# passion-v2-1.net
KiCad netlist of a schematic drawn in EAGLE
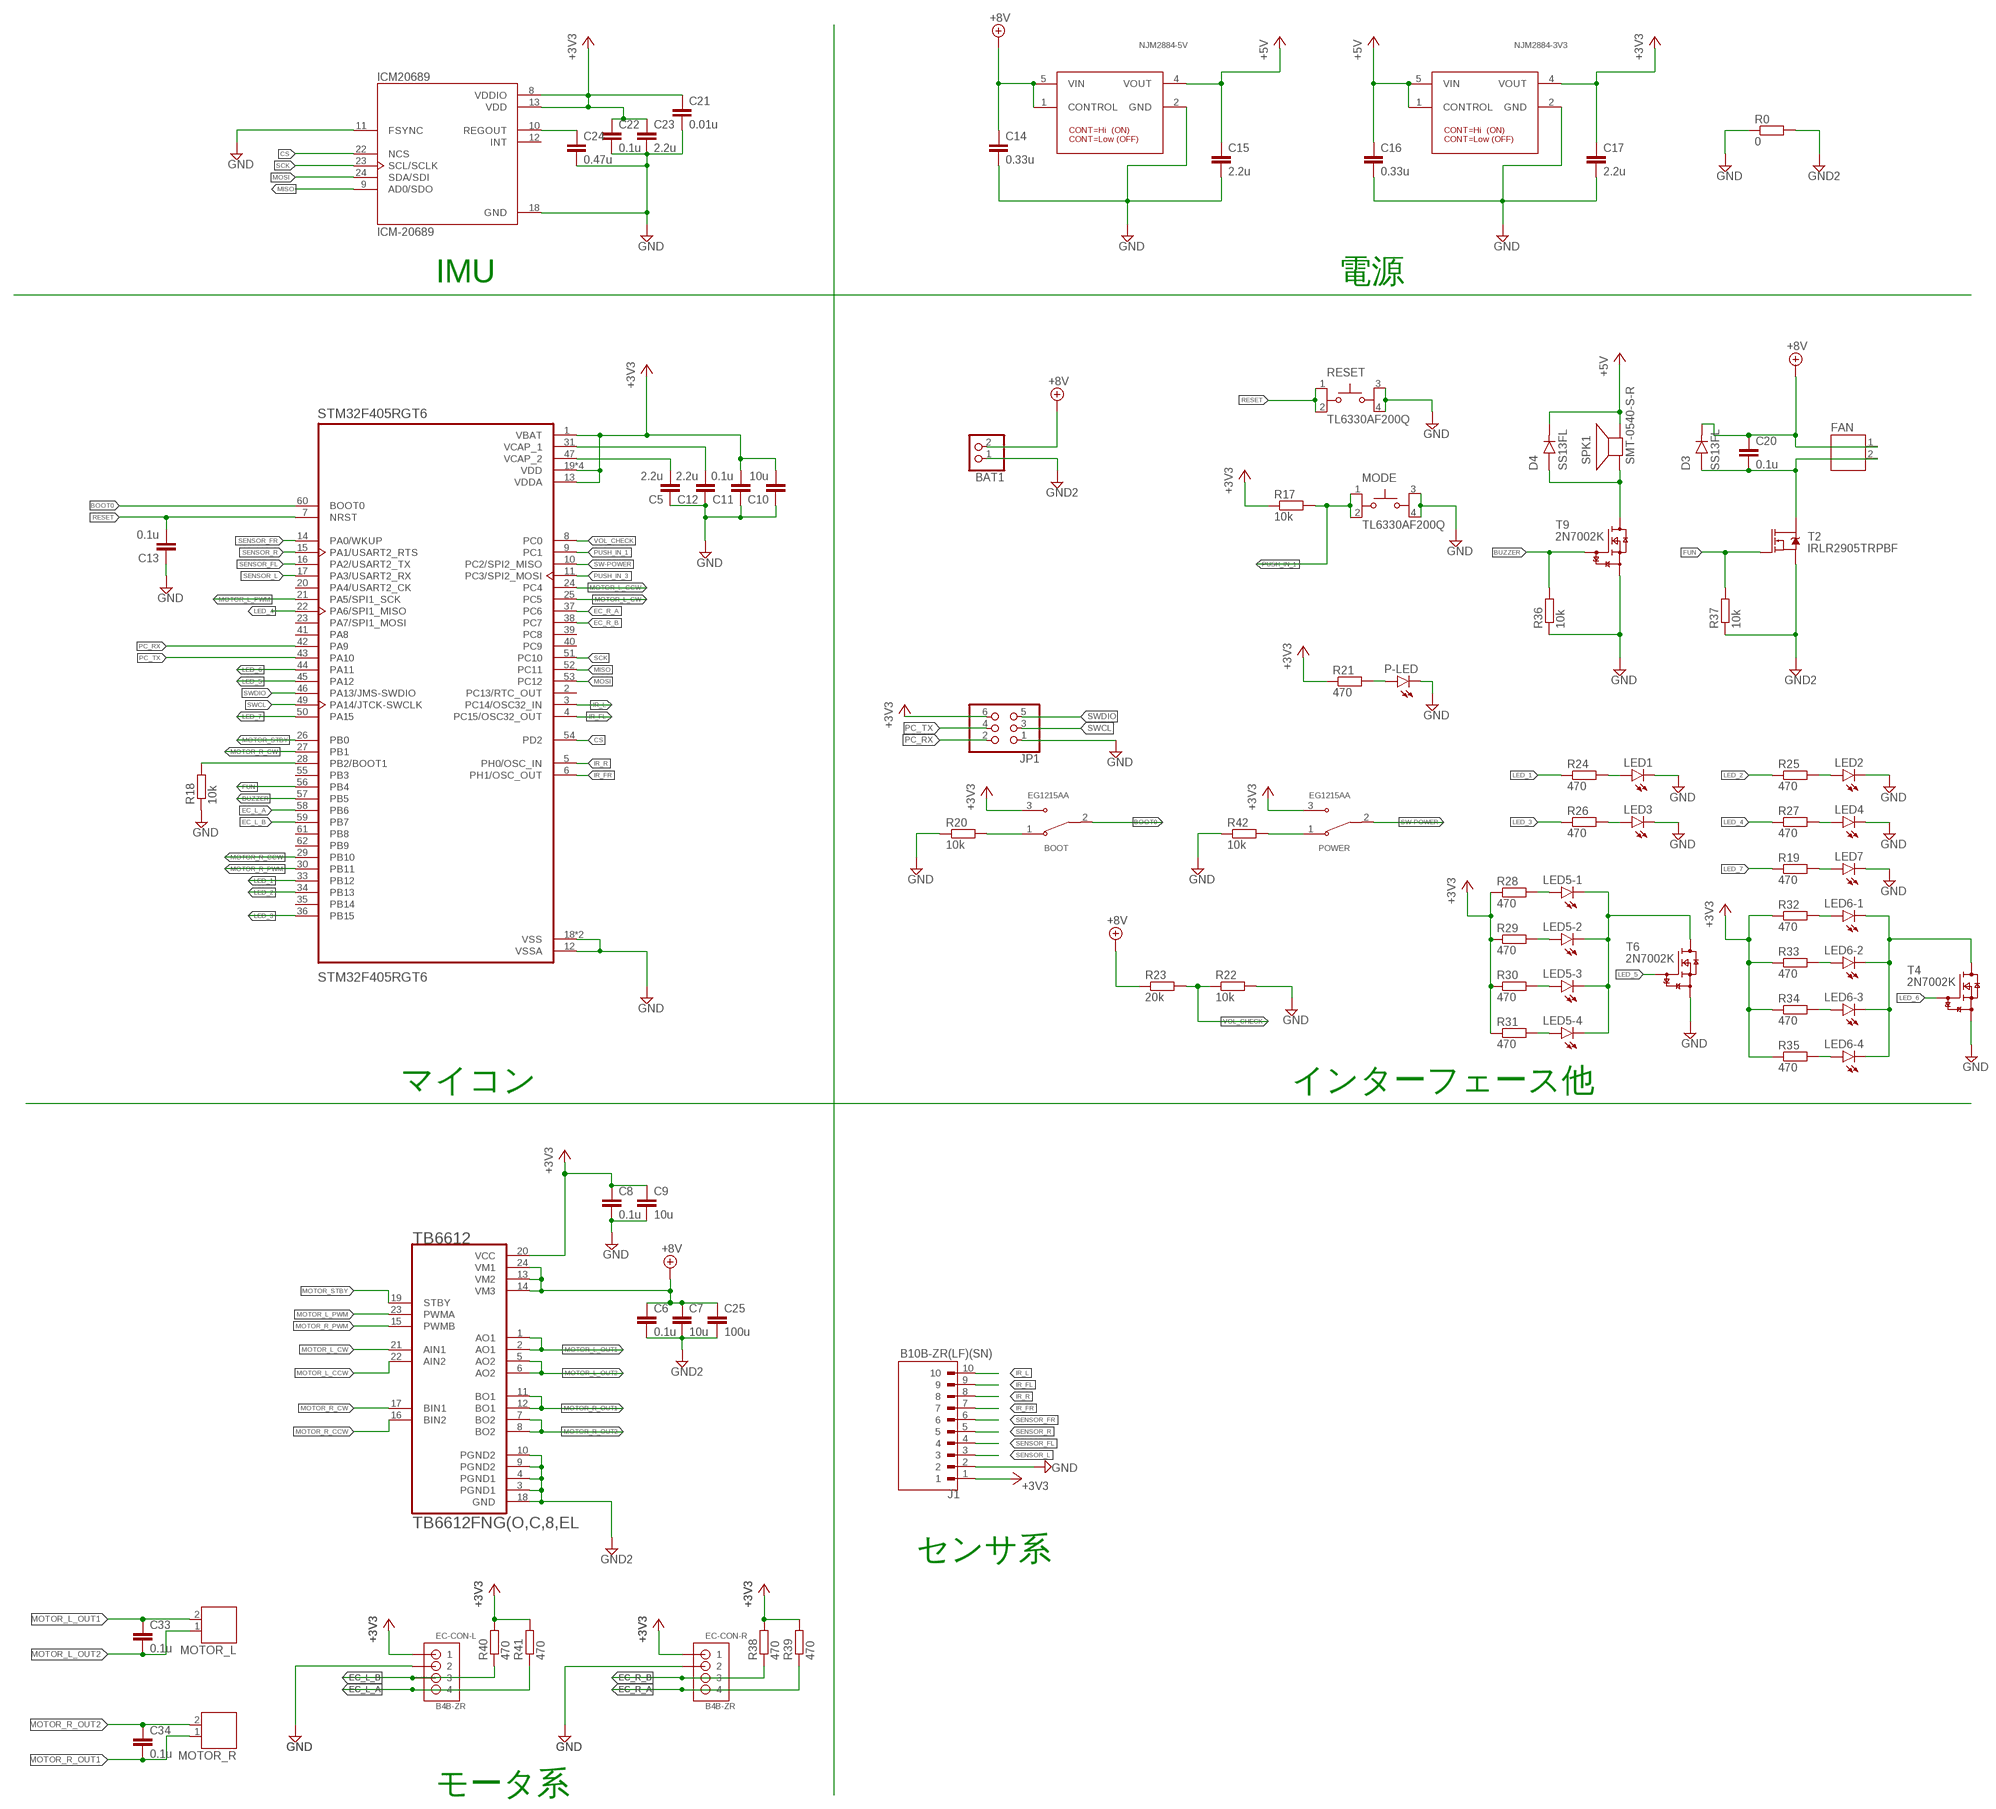
[diagram p0: schematic, sheet 1]

(export (version "E")
  (design (tool "Eeschema 10.0.6"))
  (components
    (comp (ref "BAT1")
      (value "PINHD-1X2")
      (footprint "eagle-import:1X02")
      (libsource (lib "eagle-import") (part "PINHD-1X2"))
    )
    (comp (ref "BOOT")
      (value "EG1215AA")
      (footprint "eagle-import:SW_EG1215AA")
      (fields (field (name "MF") "E-Switch"))
      (libsource (lib "eagle-import") (part "EG1215AA"))
    )
    (comp (ref "C5")
      (value "2.2u")
      (footprint "eagle-import:C0603")
      (libsource (lib "eagle-import") (part "C-EUC0603"))
    )
    (comp (ref "C6")
      (value "0.1u")
      (footprint "eagle-import:C0603")
      (libsource (lib "eagle-import") (part "C-EUC0603"))
    )
    (comp (ref "C7")
      (value "10u")
      (footprint "eagle-import:C0603")
      (libsource (lib "eagle-import") (part "C-EUC0603"))
    )
    (comp (ref "C8")
      (value "0.1u")
      (footprint "eagle-import:C0603")
      (libsource (lib "eagle-import") (part "C-EUC0603"))
    )
    (comp (ref "C9")
      (value "10u")
      (footprint "eagle-import:C0603K")
      (libsource (lib "eagle-import") (part "C-EUC0603K"))
    )
    (comp (ref "C10")
      (value "10u")
      (footprint "eagle-import:C0603")
      (libsource (lib "eagle-import") (part "C-EUC0603"))
    )
    (comp (ref "C11")
      (value "0.1u")
      (footprint "eagle-import:C0603")
      (libsource (lib "eagle-import") (part "C-EUC0603"))
    )
    (comp (ref "C12")
      (value "2.2u")
      (footprint "eagle-import:C0603")
      (libsource (lib "eagle-import") (part "C-EUC0603"))
    )
    (comp (ref "C13")
      (value "0.1u")
      (footprint "eagle-import:C0603")
      (libsource (lib "eagle-import") (part "C-EUC0603"))
    )
    (comp (ref "C14")
      (value "0.33u")
      (footprint "eagle-import:C0603")
      (libsource (lib "eagle-import") (part "C-EUC0603"))
    )
    (comp (ref "C15")
      (value "2.2u")
      (footprint "eagle-import:C0603")
      (libsource (lib "eagle-import") (part "C-EUC0603"))
    )
    (comp (ref "C16")
      (value "0.33u")
      (footprint "eagle-import:C0603")
      (libsource (lib "eagle-import") (part "C-EUC0603"))
    )
    (comp (ref "C17")
      (value "2.2u")
      (footprint "eagle-import:C0603")
      (libsource (lib "eagle-import") (part "C-EUC0603"))
    )
    (comp (ref "C20")
      (value "0.1u")
      (footprint "eagle-import:C0603")
      (libsource (lib "eagle-import") (part "C-EUC0603"))
    )
    (comp (ref "C21")
      (value "0.01u")
      (footprint "eagle-import:C0603")
      (libsource (lib "eagle-import") (part "C-EUC0603"))
    )
    (comp (ref "C22")
      (value "0.1u")
      (footprint "eagle-import:C0603")
      (libsource (lib "eagle-import") (part "C-EUC0603"))
    )
    (comp (ref "C23")
      (value "2.2u")
      (footprint "eagle-import:C0603")
      (libsource (lib "eagle-import") (part "C-EUC0603"))
    )
    (comp (ref "C24")
      (value "0.47u")
      (footprint "eagle-import:C0603")
      (libsource (lib "eagle-import") (part "C-EUC0603"))
    )
    (comp (ref "C25")
      (value "100u")
      (footprint "eagle-import:C3216")
      (libsource (lib "eagle-import") (part "C-EUC3216"))
    )
    (comp (ref "C33")
      (value "0.1u")
      (footprint "eagle-import:C0603")
      (libsource (lib "eagle-import") (part "C-EUC0603"))
    )
    (comp (ref "C34")
      (value "0.1u")
      (footprint "eagle-import:C0603")
      (libsource (lib "eagle-import") (part "C-EUC0603"))
    )
    (comp (ref "D3")
      (value "SS13FL")
      (footprint "eagle-import:SODFL3617X108N")
      (fields (field (name "MF") "ON Semiconductor"))
      (libsource (lib "eagle-import") (part "SS13FL"))
    )
    (comp (ref "D4")
      (value "SS13FL")
      (footprint "eagle-import:SODFL3617X108N")
      (fields (field (name "MF") "ON Semiconductor"))
      (libsource (lib "eagle-import") (part "SS13FL"))
    )
    (comp (ref "EC-CON-L")
      (value "B4B-ZR")
      (footprint "eagle-import:B4B-ZR")
      (libsource (lib "eagle-import") (part "B4B-ZR"))
    )
    (comp (ref "EC-CON-R")
      (value "B4B-ZR")
      (footprint "eagle-import:B4B-ZR")
      (libsource (lib "eagle-import") (part "B4B-ZR"))
    )
    (comp (ref "FAN")
      (value "JST-PH2")
      (footprint "eagle-import:JST-PH2")
      (libsource (lib "eagle-import") (part "JST-PH2"))
    )
    (comp (ref "ICM20689")
      (value "ICM-20689")
      (footprint "eagle-import:QFN50P400X400X95-24N")
      (fields (field (name "MF") "TDK InvenSense"))
      (libsource (lib "eagle-import") (part "ICM-20689"))
    )
    (comp (ref "J1")
      (value "B10B-ZR(LF)(SN)")
      (footprint "eagle-import:JST_B10B-ZR(LF)(SN)")
      (fields (field (name "MF") "JST Sales America Inc."))
      (libsource (lib "eagle-import") (part "B10B-ZR(LF)(SN)"))
    )
    (comp (ref "JP1")
      (value "PINHD-2X3")
      (footprint "eagle-import:2X03")
      (libsource (lib "eagle-import") (part "PINHD-2X3"))
    )
    (comp (ref "LED1")
      (value "LEDCHIPLED_0603")
      (footprint "eagle-import:CHIPLED_0603")
      (libsource (lib "eagle-import") (part "LEDCHIPLED_0603"))
    )
    (comp (ref "LED2")
      (value "LEDCHIPLED_0603")
      (footprint "eagle-import:CHIPLED_0603")
      (libsource (lib "eagle-import") (part "LEDCHIPLED_0603"))
    )
    (comp (ref "LED3")
      (value "LEDCHIPLED_0603")
      (footprint "eagle-import:CHIPLED_0603")
      (libsource (lib "eagle-import") (part "LEDCHIPLED_0603"))
    )
    (comp (ref "LED4")
      (value "LEDCHIPLED_0603")
      (footprint "eagle-import:CHIPLED_0603")
      (libsource (lib "eagle-import") (part "LEDCHIPLED_0603"))
    )
    (comp (ref "LED5-1")
      (value "LEDCHIPLED_0603")
      (footprint "eagle-import:CHIPLED_0603")
      (libsource (lib "eagle-import") (part "LEDCHIPLED_0603"))
    )
    (comp (ref "LED5-2")
      (value "LEDCHIPLED_0603")
      (footprint "eagle-import:CHIPLED_0603")
      (libsource (lib "eagle-import") (part "LEDCHIPLED_0603"))
    )
    (comp (ref "LED5-3")
      (value "LEDCHIPLED_0603")
      (footprint "eagle-import:CHIPLED_0603")
      (libsource (lib "eagle-import") (part "LEDCHIPLED_0603"))
    )
    (comp (ref "LED5-4")
      (value "LEDCHIPLED_0603")
      (footprint "eagle-import:CHIPLED_0603")
      (libsource (lib "eagle-import") (part "LEDCHIPLED_0603"))
    )
    (comp (ref "LED6-1")
      (value "LEDCHIPLED_0603")
      (footprint "eagle-import:CHIPLED_0603")
      (libsource (lib "eagle-import") (part "LEDCHIPLED_0603"))
    )
    (comp (ref "LED6-2")
      (value "LEDCHIPLED_0603")
      (footprint "eagle-import:CHIPLED_0603")
      (libsource (lib "eagle-import") (part "LEDCHIPLED_0603"))
    )
    (comp (ref "LED6-3")
      (value "LEDCHIPLED_0603")
      (footprint "eagle-import:CHIPLED_0603")
      (libsource (lib "eagle-import") (part "LEDCHIPLED_0603"))
    )
    (comp (ref "LED6-4")
      (value "LEDCHIPLED_0603")
      (footprint "eagle-import:CHIPLED_0603")
      (libsource (lib "eagle-import") (part "LEDCHIPLED_0603"))
    )
    (comp (ref "LED7")
      (value "LEDCHIPLED_0603")
      (footprint "eagle-import:CHIPLED_0603")
      (libsource (lib "eagle-import") (part "LEDCHIPLED_0603"))
    )
    (comp (ref "MODE")
      (value "TL6330AF200Q")
      (footprint "eagle-import:SW_TL6330AF200Q")
      (fields (field (name "MF") "E-Switch"))
      (libsource (lib "eagle-import") (part "TL6330AF200Q"))
    )
    (comp (ref "MOTOR_L")
      (value "JST-PH2")
      (footprint "eagle-import:JST-PH2")
      (libsource (lib "eagle-import") (part "JST-PH2"))
    )
    (comp (ref "MOTOR_R")
      (value "JST-PH2")
      (footprint "eagle-import:JST-PH2")
      (libsource (lib "eagle-import") (part "JST-PH2"))
    )
    (comp (ref "NJM2884-3V3")
      (value "I-10673_NJM2884U1-33")
      (footprint "eagle-import:NJM2884U1-33")
      (libsource (lib "eagle-import") (part "I-10673_NJM2884U1-33"))
    )
    (comp (ref "NJM2884-5V")
      (value "I-10673_NJM2884U1-33")
      (footprint "eagle-import:NJM2884U1-33")
      (libsource (lib "eagle-import") (part "I-10673_NJM2884U1-33"))
    )
    (comp (ref "P-LED")
      (value "LEDCHIPLED_0603")
      (footprint "eagle-import:CHIPLED_0603")
      (libsource (lib "eagle-import") (part "LEDCHIPLED_0603"))
    )
    (comp (ref "POWER")
      (value "EG1215AA")
      (footprint "eagle-import:SW_EG1215AA")
      (fields (field (name "MF") "E-Switch"))
      (libsource (lib "eagle-import") (part "EG1215AA"))
    )
    (comp (ref "R0")
      (value "0")
      (footprint "eagle-import:R0603")
      (libsource (lib "eagle-import") (part "R-EU_R0603"))
    )
    (comp (ref "R17")
      (value "10k")
      (footprint "eagle-import:R0603")
      (libsource (lib "eagle-import") (part "R-EU_R0603"))
    )
    (comp (ref "R18")
      (value "10k")
      (footprint "eagle-import:R0603")
      (libsource (lib "eagle-import") (part "R-EU_R0603"))
    )
    (comp (ref "R19")
      (value "470")
      (footprint "eagle-import:R0603")
      (libsource (lib "eagle-import") (part "R-EU_R0603"))
    )
    (comp (ref "R20")
      (value "10k")
      (footprint "eagle-import:R0603")
      (libsource (lib "eagle-import") (part "R-EU_R0603"))
    )
    (comp (ref "R21")
      (value "470")
      (footprint "eagle-import:R0603")
      (libsource (lib "eagle-import") (part "R-EU_R0603"))
    )
    (comp (ref "R22")
      (value "10k")
      (footprint "eagle-import:R0603")
      (libsource (lib "eagle-import") (part "R-EU_R0603"))
    )
    (comp (ref "R23")
      (value "20k")
      (footprint "eagle-import:R0603")
      (libsource (lib "eagle-import") (part "R-EU_R0603"))
    )
    (comp (ref "R24")
      (value "470")
      (footprint "eagle-import:R0603")
      (libsource (lib "eagle-import") (part "R-EU_R0603"))
    )
    (comp (ref "R25")
      (value "470")
      (footprint "eagle-import:R0603")
      (libsource (lib "eagle-import") (part "R-EU_R0603"))
    )
    (comp (ref "R26")
      (value "470")
      (footprint "eagle-import:R0603")
      (libsource (lib "eagle-import") (part "R-EU_R0603"))
    )
    (comp (ref "R27")
      (value "470")
      (footprint "eagle-import:R0603")
      (libsource (lib "eagle-import") (part "R-EU_R0603"))
    )
    (comp (ref "R28")
      (value "470")
      (footprint "eagle-import:R0603")
      (libsource (lib "eagle-import") (part "R-EU_R0603"))
    )
    (comp (ref "R29")
      (value "470")
      (footprint "eagle-import:R0603")
      (libsource (lib "eagle-import") (part "R-EU_R0603"))
    )
    (comp (ref "R30")
      (value "470")
      (footprint "eagle-import:R0603")
      (libsource (lib "eagle-import") (part "R-EU_R0603"))
    )
    (comp (ref "R31")
      (value "470")
      (footprint "eagle-import:R0603")
      (libsource (lib "eagle-import") (part "R-EU_R0603"))
    )
    (comp (ref "R32")
      (value "470")
      (footprint "eagle-import:R0603")
      (libsource (lib "eagle-import") (part "R-EU_R0603"))
    )
    (comp (ref "R33")
      (value "470")
      (footprint "eagle-import:R0603")
      (libsource (lib "eagle-import") (part "R-EU_R0603"))
    )
    (comp (ref "R34")
      (value "470")
      (footprint "eagle-import:R0603")
      (libsource (lib "eagle-import") (part "R-EU_R0603"))
    )
    (comp (ref "R35")
      (value "470")
      (footprint "eagle-import:R0603")
      (libsource (lib "eagle-import") (part "R-EU_R0603"))
    )
    (comp (ref "R36")
      (value "10k")
      (footprint "eagle-import:R0603")
      (libsource (lib "eagle-import") (part "R-EU_R0603"))
    )
    (comp (ref "R37")
      (value "10k")
      (footprint "eagle-import:R0603")
      (libsource (lib "eagle-import") (part "R-EU_R0603"))
    )
    (comp (ref "R38")
      (value "470")
      (footprint "eagle-import:R0402")
      (libsource (lib "eagle-import") (part "R-EU_R0402"))
    )
    (comp (ref "R39")
      (value "470")
      (footprint "eagle-import:R0402")
      (libsource (lib "eagle-import") (part "R-EU_R0402"))
    )
    (comp (ref "R40")
      (value "470")
      (footprint "eagle-import:R0402")
      (libsource (lib "eagle-import") (part "R-EU_R0402"))
    )
    (comp (ref "R41")
      (value "470")
      (footprint "eagle-import:R0402")
      (libsource (lib "eagle-import") (part "R-EU_R0402"))
    )
    (comp (ref "R42")
      (value "10k")
      (footprint "eagle-import:R0603")
      (libsource (lib "eagle-import") (part "R-EU_R0603"))
    )
    (comp (ref "RESET")
      (value "TL6330AF200Q")
      (footprint "eagle-import:SW_TL6330AF200Q")
      (fields (field (name "MF") "E-Switch"))
      (libsource (lib "eagle-import") (part "TL6330AF200Q"))
    )
    (comp (ref "SPK1")
      (value "SMT-0540-S-R")
      (footprint "eagle-import:SMT-0540-S-R")
      (fields (field (name "DIGI-KEY_PART_NUMBER") "668-1060-1-ND") (field (name "MF") "PUI"))
      (libsource (lib "eagle-import") (part "SMT-0540-S-R"))
    )
    (comp (ref "STM32F405RGT6")
      (value "STM32F405RGT6")
      (footprint "eagle-import:QFP50P1200X1200X160-64N")
      (fields (field (name "MF") "STMicroelectronics"))
      (libsource (lib "eagle-import") (part "STM32F405RGT6"))
    )
    (comp (ref "T2")
      (value "IRLR2905TRPBF")
      (footprint "eagle-import:TO252-3")
      (fields (field (name "MF") "Infineon Technologies"))
      (libsource (lib "eagle-import") (part "IRLR2905TRPBF"))
    )
    (comp (ref "T4")
      (value "2N7002K")
      (footprint "eagle-import:SOT23")
      (libsource (lib "eagle-import") (part "2N7002K"))
    )
    (comp (ref "T6")
      (value "2N7002K")
      (footprint "eagle-import:SOT23")
      (libsource (lib "eagle-import") (part "2N7002K"))
    )
    (comp (ref "T9")
      (value "2N7002K")
      (footprint "eagle-import:SOT23")
      (libsource (lib "eagle-import") (part "2N7002K"))
    )
    (comp (ref "TB6612")
      (value "TB6612FNG(O,C,8,EL")
      (footprint "eagle-import:SOP65P760X160-24N")
      (fields (field (name "MF") "Toshiba"))
      (libsource (lib "eagle-import") (part "TB6612FNG(O,C,8,EL"))
    )
  )
  (nets
    (net (code "1") (name "+3V3") (class "Default")
      (node (ref "BOOT") (pin "3") (pinfunction "3_3") (pintype "passive"))
      (node (ref "C10") (pin "2") (pinfunction "2_2") (pintype "passive"))
      (node (ref "C11") (pin "2") (pinfunction "2_2") (pintype "passive"))
      (node (ref "C17") (pin "1") (pinfunction "1_1") (pintype "passive"))
      (node (ref "C21") (pin "1") (pinfunction "1_1") (pintype "passive"))
      (node (ref "C22") (pin "1") (pinfunction "1_1") (pintype "passive"))
      (node (ref "C23") (pin "1") (pinfunction "1_1") (pintype "passive"))
      (node (ref "C8") (pin "1") (pinfunction "1_1") (pintype "passive"))
      (node (ref "C9") (pin "1") (pinfunction "1_1") (pintype "passive"))
      (node (ref "EC-CON-L") (pin "1") (pinfunction "1_1") (pintype "bidirectional"))
      (node (ref "EC-CON-R") (pin "1") (pinfunction "1_1") (pintype "bidirectional"))
      (node (ref "ICM20689") (pin "13") (pinfunction "VDD_13") (pintype "power_in"))
      (node (ref "ICM20689") (pin "8") (pinfunction "VDDIO_8") (pintype "power_in"))
      (node (ref "J1") (pin "1") (pinfunction "1_1") (pintype "passive"))
      (node (ref "JP1") (pin "6") (pinfunction "6_6") (pintype "passive"))
      (node (ref "NJM2884-3V3") (pin "4") (pinfunction "VOUT_4") (pintype "bidirectional"))
      (node (ref "POWER") (pin "3") (pinfunction "3_3") (pintype "passive"))
      (node (ref "R17") (pin "1") (pinfunction "1_1") (pintype "passive"))
      (node (ref "R21") (pin "1") (pinfunction "1_1") (pintype "passive"))
      (node (ref "R28") (pin "1") (pinfunction "1_1") (pintype "passive"))
      (node (ref "R29") (pin "1") (pinfunction "1_1") (pintype "passive"))
      (node (ref "R30") (pin "1") (pinfunction "1_1") (pintype "passive"))
      (node (ref "R31") (pin "1") (pinfunction "1_1") (pintype "passive"))
      (node (ref "R32") (pin "1") (pinfunction "1_1") (pintype "passive"))
      (node (ref "R33") (pin "1") (pinfunction "1_1") (pintype "passive"))
      (node (ref "R34") (pin "1") (pinfunction "1_1") (pintype "passive"))
      (node (ref "R35") (pin "1") (pinfunction "1_1") (pintype "passive"))
      (node (ref "R38") (pin "2") (pinfunction "2_2") (pintype "passive"))
      (node (ref "R39") (pin "2") (pinfunction "2_2") (pintype "passive"))
      (node (ref "R40") (pin "2") (pinfunction "2_2") (pintype "passive"))
      (node (ref "R41") (pin "2") (pinfunction "2_2") (pintype "passive"))
      (node (ref "STM32F405RGT6") (pin "1") (pinfunction "VBAT_1") (pintype "power_in"))
      (node (ref "STM32F405RGT6") (pin "13") (pinfunction "VDDA_13") (pintype "power_in"))
      (node (ref "STM32F405RGT6") (pin "19") (pinfunction "VDD_19") (pintype "power_in"))
      (node (ref "STM32F405RGT6") (pin "32") (pinfunction "VDD_32") (pintype "power_in"))
      (node (ref "STM32F405RGT6") (pin "48") (pinfunction "VDD_48") (pintype "power_in"))
      (node (ref "STM32F405RGT6") (pin "64") (pinfunction "VDD_64") (pintype "power_in"))
      (node (ref "TB6612") (pin "20") (pinfunction "VCC_20") (pintype "power_in"))
    )
    (net (code "2") (name "+5V") (class "Default")
      (node (ref "C15") (pin "1") (pinfunction "1_1") (pintype "passive"))
      (node (ref "C16") (pin "1") (pinfunction "1_1") (pintype "passive"))
      (node (ref "D4") (pin "C") (pinfunction "C_C") (pintype "passive"))
      (node (ref "NJM2884-3V3") (pin "1") (pinfunction "CONTROL_1") (pintype "bidirectional"))
      (node (ref "NJM2884-3V3") (pin "5") (pinfunction "VIN_5") (pintype "bidirectional"))
      (node (ref "NJM2884-5V") (pin "4") (pinfunction "VOUT_4") (pintype "bidirectional"))
      (node (ref "SPK1") (pin "+") (pinfunction "-_+") (pintype "passive"))
    )
    (net (code "3") (name "+8V") (class "Default")
      (node (ref "BAT1") (pin "2") (pinfunction "2_2") (pintype "passive"))
      (node (ref "C14") (pin "1") (pinfunction "1_1") (pintype "passive"))
      (node (ref "C20") (pin "1") (pinfunction "1_1") (pintype "passive"))
      (node (ref "C25") (pin "1") (pinfunction "1_1") (pintype "passive"))
      (node (ref "C6") (pin "1") (pinfunction "1_1") (pintype "passive"))
      (node (ref "C7") (pin "1") (pinfunction "1_1") (pintype "passive"))
      (node (ref "D3") (pin "C") (pinfunction "C_C") (pintype "passive"))
      (node (ref "FAN") (pin "1") (pinfunction "1_1") (pintype "passive"))
      (node (ref "NJM2884-5V") (pin "1") (pinfunction "CONTROL_1") (pintype "bidirectional"))
      (node (ref "NJM2884-5V") (pin "5") (pinfunction "VIN_5") (pintype "bidirectional"))
      (node (ref "R23") (pin "1") (pinfunction "1_1") (pintype "passive"))
      (node (ref "TB6612") (pin "13") (pinfunction "VM2_13") (pintype "power_in"))
      (node (ref "TB6612") (pin "14") (pinfunction "VM3_14") (pintype "power_in"))
      (node (ref "TB6612") (pin "24") (pinfunction "VM1_24") (pintype "power_in"))
    )
    (net (code "4") (name "BOOT0") (class "Default")
      (node (ref "BOOT") (pin "2") (pinfunction "2_2") (pintype "passive"))
      (node (ref "STM32F405RGT6") (pin "60") (pinfunction "BOOT0_60") (pintype "bidirectional"))
    )
    (net (code "5") (name "BUZZER") (class "Default")
      (node (ref "R36") (pin "2") (pinfunction "2_2") (pintype "passive"))
      (node (ref "STM32F405RGT6") (pin "57") (pinfunction "PB5_57") (pintype "bidirectional"))
      (node (ref "T9") (pin "1") (pinfunction "G_1") (pintype "passive"))
    )
    (net (code "6") (name "CS") (class "Default")
      (node (ref "ICM20689") (pin "22") (pinfunction "NCS_22") (pintype "input"))
      (node (ref "STM32F405RGT6") (pin "54") (pinfunction "PD2_54") (pintype "bidirectional"))
    )
    (net (code "7") (name "EC_L_A") (class "Default")
      (node (ref "EC-CON-L") (pin "4") (pinfunction "4_4") (pintype "bidirectional"))
      (node (ref "R41") (pin "1") (pinfunction "1_1") (pintype "passive"))
      (node (ref "STM32F405RGT6") (pin "58") (pinfunction "PB6_58") (pintype "bidirectional"))
    )
    (net (code "8") (name "EC_L_B") (class "Default")
      (node (ref "EC-CON-L") (pin "3") (pinfunction "3_3") (pintype "bidirectional"))
      (node (ref "R40") (pin "1") (pinfunction "1_1") (pintype "passive"))
      (node (ref "STM32F405RGT6") (pin "59") (pinfunction "PB7_59") (pintype "bidirectional"))
    )
    (net (code "9") (name "EC_R_A") (class "Default")
      (node (ref "EC-CON-R") (pin "4") (pinfunction "4_4") (pintype "bidirectional"))
      (node (ref "R39") (pin "1") (pinfunction "1_1") (pintype "passive"))
      (node (ref "STM32F405RGT6") (pin "37") (pinfunction "PC6_37") (pintype "bidirectional"))
    )
    (net (code "10") (name "EC_R_B") (class "Default")
      (node (ref "EC-CON-R") (pin "3") (pinfunction "3_3") (pintype "bidirectional"))
      (node (ref "R38") (pin "1") (pinfunction "1_1") (pintype "passive"))
      (node (ref "STM32F405RGT6") (pin "38") (pinfunction "PC7_38") (pintype "bidirectional"))
    )
    (net (code "11") (name "FUN") (class "Default")
      (node (ref "R37") (pin "2") (pinfunction "2_2") (pintype "passive"))
      (node (ref "STM32F405RGT6") (pin "56") (pinfunction "PB4_56") (pintype "bidirectional"))
      (node (ref "T2") (pin "1") (pinfunction "G_1") (pintype "bidirectional"))
    )
    (net (code "12") (name "GND") (class "Default")
      (node (ref "C10") (pin "1") (pinfunction "1_1") (pintype "passive"))
      (node (ref "C11") (pin "1") (pinfunction "1_1") (pintype "passive"))
      (node (ref "C12") (pin "1") (pinfunction "1_1") (pintype "passive"))
      (node (ref "C13") (pin "1") (pinfunction "1_1") (pintype "passive"))
      (node (ref "C14") (pin "2") (pinfunction "2_2") (pintype "passive"))
      (node (ref "C15") (pin "2") (pinfunction "2_2") (pintype "passive"))
      (node (ref "C16") (pin "2") (pinfunction "2_2") (pintype "passive"))
      (node (ref "C17") (pin "2") (pinfunction "2_2") (pintype "passive"))
      (node (ref "C21") (pin "2") (pinfunction "2_2") (pintype "passive"))
      (node (ref "C22") (pin "2") (pinfunction "2_2") (pintype "passive"))
      (node (ref "C23") (pin "2") (pinfunction "2_2") (pintype "passive"))
      (node (ref "C24") (pin "2") (pinfunction "2_2") (pintype "passive"))
      (node (ref "C5") (pin "1") (pinfunction "1_1") (pintype "passive"))
      (node (ref "C8") (pin "2") (pinfunction "2_2") (pintype "passive"))
      (node (ref "C9") (pin "2") (pinfunction "2_2") (pintype "passive"))
      (node (ref "EC-CON-L") (pin "2") (pinfunction "2_2") (pintype "bidirectional"))
      (node (ref "EC-CON-R") (pin "2") (pinfunction "2_2") (pintype "bidirectional"))
      (node (ref "ICM20689") (pin "11") (pinfunction "FSYNC_11") (pintype "input"))
      (node (ref "ICM20689") (pin "18") (pinfunction "GND_18") (pintype "power_in"))
      (node (ref "J1") (pin "2") (pinfunction "2_2") (pintype "passive"))
      (node (ref "JP1") (pin "1") (pinfunction "1_1") (pintype "passive"))
      (node (ref "LED1") (pin "C") (pinfunction "C_C") (pintype "passive"))
      (node (ref "LED2") (pin "C") (pinfunction "C_C") (pintype "passive"))
      (node (ref "LED3") (pin "C") (pinfunction "C_C") (pintype "passive"))
      (node (ref "LED4") (pin "C") (pinfunction "C_C") (pintype "passive"))
      (node (ref "LED7") (pin "C") (pinfunction "C_C") (pintype "passive"))
      (node (ref "MODE") (pin "3") (pinfunction "3_3") (pintype "passive"))
      (node (ref "MODE") (pin "4") (pinfunction "4_4") (pintype "passive"))
      (node (ref "NJM2884-3V3") (pin "2") (pinfunction "GND_2") (pintype "bidirectional"))
      (node (ref "NJM2884-5V") (pin "2") (pinfunction "GND_2") (pintype "bidirectional"))
      (node (ref "P-LED") (pin "C") (pinfunction "C_C") (pintype "passive"))
      (node (ref "R0") (pin "1") (pinfunction "1_1") (pintype "passive"))
      (node (ref "R18") (pin "1") (pinfunction "1_1") (pintype "passive"))
      (node (ref "R20") (pin "1") (pinfunction "1_1") (pintype "passive"))
      (node (ref "R22") (pin "2") (pinfunction "2_2") (pintype "passive"))
      (node (ref "R36") (pin "1") (pinfunction "1_1") (pintype "passive"))
      (node (ref "R42") (pin "1") (pinfunction "1_1") (pintype "passive"))
      (node (ref "RESET") (pin "3") (pinfunction "3_3") (pintype "passive"))
      (node (ref "RESET") (pin "4") (pinfunction "4_4") (pintype "passive"))
      (node (ref "STM32F405RGT6") (pin "12") (pinfunction "VSSA_12") (pintype "power_in"))
      (node (ref "STM32F405RGT6") (pin "18") (pinfunction "VSS_18") (pintype "power_in"))
      (node (ref "STM32F405RGT6") (pin "63") (pinfunction "VSS_63") (pintype "power_in"))
      (node (ref "T4") (pin "2") (pinfunction "S_2") (pintype "passive"))
      (node (ref "T6") (pin "2") (pinfunction "S_2") (pintype "passive"))
      (node (ref "T9") (pin "2") (pinfunction "S_2") (pintype "passive"))
    )
    (net (code "13") (name "GND2") (class "Default")
      (node (ref "BAT1") (pin "1") (pinfunction "1_1") (pintype "passive"))
      (node (ref "C25") (pin "2") (pinfunction "2_2") (pintype "passive"))
      (node (ref "C6") (pin "2") (pinfunction "2_2") (pintype "passive"))
      (node (ref "C7") (pin "2") (pinfunction "2_2") (pintype "passive"))
      (node (ref "R0") (pin "2") (pinfunction "2_2") (pintype "passive"))
      (node (ref "R37") (pin "1") (pinfunction "1_1") (pintype "passive"))
      (node (ref "T2") (pin "3") (pinfunction "S_3") (pintype "bidirectional"))
      (node (ref "TB6612") (pin "10") (pinfunction "PGND2_10") (pintype "passive"))
      (node (ref "TB6612") (pin "18") (pinfunction "GND_18") (pintype "passive"))
      (node (ref "TB6612") (pin "3") (pinfunction "PGND1_3") (pintype "passive"))
      (node (ref "TB6612") (pin "4") (pinfunction "PGND1_4") (pintype "passive"))
      (node (ref "TB6612") (pin "9") (pinfunction "PGND2_9") (pintype "passive"))
    )
    (net (code "14") (name "IR_FL") (class "Default")
      (node (ref "J1") (pin "9") (pinfunction "9_9") (pintype "passive"))
      (node (ref "STM32F405RGT6") (pin "4") (pinfunction "PC15/OSC32_OUT_4") (pintype "bidirectional"))
    )
    (net (code "15") (name "IR_FR") (class "Default")
      (node (ref "J1") (pin "7") (pinfunction "7_7") (pintype "passive"))
      (node (ref "STM32F405RGT6") (pin "6") (pinfunction "PH1/OSC_OUT_6") (pintype "bidirectional"))
    )
    (net (code "16") (name "IR_L") (class "Default")
      (node (ref "J1") (pin "10") (pinfunction "10_10") (pintype "passive"))
      (node (ref "STM32F405RGT6") (pin "3") (pinfunction "PC14/OSC32_IN_3") (pintype "bidirectional"))
    )
    (net (code "17") (name "IR_R") (class "Default")
      (node (ref "J1") (pin "8") (pinfunction "8_8") (pintype "passive"))
      (node (ref "STM32F405RGT6") (pin "5") (pinfunction "PH0/OSC_IN_5") (pintype "bidirectional"))
    )
    (net (code "18") (name "LED_1") (class "Default")
      (node (ref "R24") (pin "1") (pinfunction "1_1") (pintype "passive"))
      (node (ref "STM32F405RGT6") (pin "33") (pinfunction "PB12_33") (pintype "bidirectional"))
    )
    (net (code "19") (name "LED_2") (class "Default")
      (node (ref "R25") (pin "1") (pinfunction "1_1") (pintype "passive"))
      (node (ref "STM32F405RGT6") (pin "34") (pinfunction "PB13_34") (pintype "bidirectional"))
    )
    (net (code "20") (name "LED_3") (class "Default")
      (node (ref "R26") (pin "1") (pinfunction "1_1") (pintype "passive"))
      (node (ref "STM32F405RGT6") (pin "36") (pinfunction "PB15_36") (pintype "bidirectional"))
    )
    (net (code "21") (name "LED_4") (class "Default")
      (node (ref "R27") (pin "1") (pinfunction "1_1") (pintype "passive"))
      (node (ref "STM32F405RGT6") (pin "22") (pinfunction "PA6/SPI1_MISO_22") (pintype "bidirectional"))
    )
    (net (code "22") (name "LED_5") (class "Default")
      (node (ref "STM32F405RGT6") (pin "45") (pinfunction "PA12_45") (pintype "bidirectional"))
      (node (ref "T6") (pin "1") (pinfunction "G_1") (pintype "passive"))
    )
    (net (code "23") (name "LED_6") (class "Default")
      (node (ref "STM32F405RGT6") (pin "44") (pinfunction "PA11_44") (pintype "bidirectional"))
      (node (ref "T4") (pin "1") (pinfunction "G_1") (pintype "passive"))
    )
    (net (code "24") (name "LED_7") (class "Default")
      (node (ref "R19") (pin "1") (pinfunction "1_1") (pintype "passive"))
      (node (ref "STM32F405RGT6") (pin "50") (pinfunction "PA15_50") (pintype "bidirectional"))
    )
    (net (code "25") (name "MISO") (class "Default")
      (node (ref "ICM20689") (pin "9") (pinfunction "AD0/SDO_9") (pintype "bidirectional"))
      (node (ref "STM32F405RGT6") (pin "52") (pinfunction "PC11_52") (pintype "bidirectional"))
    )
    (net (code "26") (name "MOSI") (class "Default")
      (node (ref "ICM20689") (pin "24") (pinfunction "SDA/SDI_24") (pintype "bidirectional"))
      (node (ref "STM32F405RGT6") (pin "53") (pinfunction "PC12_53") (pintype "bidirectional"))
    )
    (net (code "27") (name "MOTOR_L_CCW") (class "Default")
      (node (ref "STM32F405RGT6") (pin "24") (pinfunction "PC4_24") (pintype "bidirectional"))
      (node (ref "TB6612") (pin "22") (pinfunction "AIN2_22") (pintype "input"))
    )
    (net (code "28") (name "MOTOR_L_CW") (class "Default")
      (node (ref "STM32F405RGT6") (pin "25") (pinfunction "PC5_25") (pintype "bidirectional"))
      (node (ref "TB6612") (pin "21") (pinfunction "AIN1_21") (pintype "input"))
    )
    (net (code "29") (name "MOTOR_L_OUT1") (class "Default")
      (node (ref "C33") (pin "1") (pinfunction "1_1") (pintype "passive"))
      (node (ref "MOTOR_L") (pin "2") (pinfunction "2_2") (pintype "passive"))
      (node (ref "TB6612") (pin "1") (pinfunction "AO1_1") (pintype "output"))
      (node (ref "TB6612") (pin "2") (pinfunction "AO1_2") (pintype "output"))
    )
    (net (code "30") (name "MOTOR_L_OUT2") (class "Default")
      (node (ref "C33") (pin "2") (pinfunction "2_2") (pintype "passive"))
      (node (ref "MOTOR_L") (pin "1") (pinfunction "1_1") (pintype "passive"))
      (node (ref "TB6612") (pin "5") (pinfunction "AO2_5") (pintype "output"))
      (node (ref "TB6612") (pin "6") (pinfunction "AO2_6") (pintype "output"))
    )
    (net (code "31") (name "MOTOR_L_PWM") (class "Default")
      (node (ref "STM32F405RGT6") (pin "21") (pinfunction "PA5/SPI1_SCK_21") (pintype "bidirectional"))
      (node (ref "TB6612") (pin "23") (pinfunction "PWMA_23") (pintype "input"))
    )
    (net (code "32") (name "MOTOR_R_CCW") (class "Default")
      (node (ref "STM32F405RGT6") (pin "29") (pinfunction "PB10_29") (pintype "bidirectional"))
      (node (ref "TB6612") (pin "16") (pinfunction "BIN2_16") (pintype "input"))
    )
    (net (code "33") (name "MOTOR_R_CW") (class "Default")
      (node (ref "STM32F405RGT6") (pin "27") (pinfunction "PB1_27") (pintype "bidirectional"))
      (node (ref "TB6612") (pin "17") (pinfunction "BIN1_17") (pintype "input"))
    )
    (net (code "34") (name "MOTOR_R_OUT1") (class "Default")
      (node (ref "C34") (pin "2") (pinfunction "2_2") (pintype "passive"))
      (node (ref "MOTOR_R") (pin "1") (pinfunction "1_1") (pintype "passive"))
      (node (ref "TB6612") (pin "11") (pinfunction "BO1_11") (pintype "output"))
      (node (ref "TB6612") (pin "12") (pinfunction "BO1_12") (pintype "output"))
    )
    (net (code "35") (name "MOTOR_R_OUT2") (class "Default")
      (node (ref "C34") (pin "1") (pinfunction "1_1") (pintype "passive"))
      (node (ref "MOTOR_R") (pin "2") (pinfunction "2_2") (pintype "passive"))
      (node (ref "TB6612") (pin "7") (pinfunction "BO2_7") (pintype "output"))
      (node (ref "TB6612") (pin "8") (pinfunction "BO2_8") (pintype "output"))
    )
    (net (code "36") (name "MOTOR_R_PWM") (class "Default")
      (node (ref "STM32F405RGT6") (pin "30") (pinfunction "PB11_30") (pintype "bidirectional"))
      (node (ref "TB6612") (pin "15") (pinfunction "PWMB_15") (pintype "input"))
    )
    (net (code "37") (name "MOTOR_STBY") (class "Default")
      (node (ref "STM32F405RGT6") (pin "26") (pinfunction "PB0_26") (pintype "bidirectional"))
      (node (ref "TB6612") (pin "19") (pinfunction "STBY_19") (pintype "input"))
    )
    (net (code "38") (name "Net-(BOOT-Pad1)") (class "Default")
      (node (ref "BOOT") (pin "1") (pinfunction "1_1") (pintype "passive"))
      (node (ref "R20") (pin "2") (pinfunction "2_2") (pintype "passive"))
    )
    (net (code "39") (name "Net-(C20-Pad2)") (class "Default")
      (node (ref "C20") (pin "2") (pinfunction "2_2") (pintype "passive"))
      (node (ref "D3") (pin "A") (pinfunction "A_A") (pintype "passive"))
      (node (ref "FAN") (pin "2") (pinfunction "2_2") (pintype "passive"))
      (node (ref "T2") (pin "2") (pinfunction "D_2") (pintype "bidirectional"))
      (node (ref "T2") (pin "PAD") (pinfunction "D_PAD") (pintype "bidirectional"))
    )
    (net (code "40") (name "Net-(ICM20689-REGOUT)") (class "Default")
      (node (ref "C24") (pin "1") (pinfunction "1_1") (pintype "passive"))
      (node (ref "ICM20689") (pin "10") (pinfunction "REGOUT_10") (pintype "output"))
    )
    (net (code "41") (name "Net-(LED1-PadA)") (class "Default")
      (node (ref "LED1") (pin "A") (pinfunction "A_A") (pintype "passive"))
      (node (ref "R24") (pin "2") (pinfunction "2_2") (pintype "passive"))
    )
    (net (code "42") (name "Net-(LED2-PadA)") (class "Default")
      (node (ref "LED2") (pin "A") (pinfunction "A_A") (pintype "passive"))
      (node (ref "R25") (pin "2") (pinfunction "2_2") (pintype "passive"))
    )
    (net (code "43") (name "Net-(LED3-PadA)") (class "Default")
      (node (ref "LED3") (pin "A") (pinfunction "A_A") (pintype "passive"))
      (node (ref "R26") (pin "2") (pinfunction "2_2") (pintype "passive"))
    )
    (net (code "44") (name "Net-(LED4-PadA)") (class "Default")
      (node (ref "LED4") (pin "A") (pinfunction "A_A") (pintype "passive"))
      (node (ref "R27") (pin "2") (pinfunction "2_2") (pintype "passive"))
    )
    (net (code "45") (name "Net-(LED5-1-PadA)") (class "Default")
      (node (ref "LED5-1") (pin "A") (pinfunction "A_A") (pintype "passive"))
      (node (ref "R28") (pin "2") (pinfunction "2_2") (pintype "passive"))
    )
    (net (code "46") (name "Net-(LED5-2-PadA)") (class "Default")
      (node (ref "LED5-2") (pin "A") (pinfunction "A_A") (pintype "passive"))
      (node (ref "R29") (pin "2") (pinfunction "2_2") (pintype "passive"))
    )
    (net (code "47") (name "Net-(LED5-3-PadA)") (class "Default")
      (node (ref "LED5-3") (pin "A") (pinfunction "A_A") (pintype "passive"))
      (node (ref "R30") (pin "2") (pinfunction "2_2") (pintype "passive"))
    )
    (net (code "48") (name "Net-(LED5-4-PadA)") (class "Default")
      (node (ref "LED5-4") (pin "A") (pinfunction "A_A") (pintype "passive"))
      (node (ref "R31") (pin "2") (pinfunction "2_2") (pintype "passive"))
    )
    (net (code "49") (name "Net-(LED6-1-PadA)") (class "Default")
      (node (ref "LED6-1") (pin "A") (pinfunction "A_A") (pintype "passive"))
      (node (ref "R32") (pin "2") (pinfunction "2_2") (pintype "passive"))
    )
    (net (code "50") (name "Net-(LED6-2-PadA)") (class "Default")
      (node (ref "LED6-2") (pin "A") (pinfunction "A_A") (pintype "passive"))
      (node (ref "R33") (pin "2") (pinfunction "2_2") (pintype "passive"))
    )
    (net (code "51") (name "Net-(LED6-3-PadA)") (class "Default")
      (node (ref "LED6-3") (pin "A") (pinfunction "A_A") (pintype "passive"))
      (node (ref "R34") (pin "2") (pinfunction "2_2") (pintype "passive"))
    )
    (net (code "52") (name "Net-(LED6-4-PadA)") (class "Default")
      (node (ref "LED6-4") (pin "A") (pinfunction "A_A") (pintype "passive"))
      (node (ref "R35") (pin "2") (pinfunction "2_2") (pintype "passive"))
    )
    (net (code "53") (name "Net-(LED7-PadA)") (class "Default")
      (node (ref "LED7") (pin "A") (pinfunction "A_A") (pintype "passive"))
      (node (ref "R19") (pin "2") (pinfunction "2_2") (pintype "passive"))
    )
    (net (code "54") (name "Net-(P-LED-PadA)") (class "Default")
      (node (ref "P-LED") (pin "A") (pinfunction "A_A") (pintype "passive"))
      (node (ref "R21") (pin "2") (pinfunction "2_2") (pintype "passive"))
    )
    (net (code "55") (name "Net-(POWER-Pad1)") (class "Default")
      (node (ref "POWER") (pin "1") (pinfunction "1_1") (pintype "passive"))
      (node (ref "R42") (pin "2") (pinfunction "2_2") (pintype "passive"))
    )
    (net (code "56") (name "Net-(SPK1-+)") (class "Default")
      (node (ref "D4") (pin "A") (pinfunction "A_A") (pintype "passive"))
      (node (ref "SPK1") (pin "-") (pinfunction "+_-") (pintype "passive"))
      (node (ref "T9") (pin "3") (pinfunction "D_3") (pintype "passive"))
    )
    (net (code "57") (name "Net-(STM32F405RGT6-PB2{slash}BOOT1)") (class "Default")
      (node (ref "R18") (pin "2") (pinfunction "2_2") (pintype "passive"))
      (node (ref "STM32F405RGT6") (pin "28") (pinfunction "PB2/BOOT1_28") (pintype "bidirectional"))
    )
    (net (code "58") (name "Net-(STM32F405RGT6-VCAP_1)") (class "Default")
      (node (ref "C12") (pin "2") (pinfunction "2_2") (pintype "passive"))
      (node (ref "STM32F405RGT6") (pin "31") (pinfunction "VCAP_1_31") (pintype "power_in"))
    )
    (net (code "59") (name "Net-(STM32F405RGT6-VCAP_2)") (class "Default")
      (node (ref "C5") (pin "2") (pinfunction "2_2") (pintype "passive"))
      (node (ref "STM32F405RGT6") (pin "47") (pinfunction "VCAP_2_47") (pintype "power_in"))
    )
    (net (code "60") (name "Net-(T4-D)") (class "Default")
      (node (ref "LED6-1") (pin "C") (pinfunction "C_C") (pintype "passive"))
      (node (ref "LED6-2") (pin "C") (pinfunction "C_C") (pintype "passive"))
      (node (ref "LED6-3") (pin "C") (pinfunction "C_C") (pintype "passive"))
      (node (ref "LED6-4") (pin "C") (pinfunction "C_C") (pintype "passive"))
      (node (ref "T4") (pin "3") (pinfunction "D_3") (pintype "passive"))
    )
    (net (code "61") (name "Net-(T6-D)") (class "Default")
      (node (ref "LED5-1") (pin "C") (pinfunction "C_C") (pintype "passive"))
      (node (ref "LED5-2") (pin "C") (pinfunction "C_C") (pintype "passive"))
      (node (ref "LED5-3") (pin "C") (pinfunction "C_C") (pintype "passive"))
      (node (ref "LED5-4") (pin "C") (pinfunction "C_C") (pintype "passive"))
      (node (ref "T6") (pin "3") (pinfunction "D_3") (pintype "passive"))
    )
    (net (code "62") (name "PC_RX") (class "Default")
      (node (ref "JP1") (pin "2") (pinfunction "2_2") (pintype "passive"))
      (node (ref "STM32F405RGT6") (pin "42") (pinfunction "PA9_42") (pintype "bidirectional"))
    )
    (net (code "63") (name "PC_TX") (class "Default")
      (node (ref "JP1") (pin "4") (pinfunction "4_4") (pintype "passive"))
      (node (ref "STM32F405RGT6") (pin "43") (pinfunction "PA10_43") (pintype "bidirectional"))
    )
    (net (code "64") (name "PUSH_IN_1") (class "Default")
      (node (ref "MODE") (pin "1") (pinfunction "1_1") (pintype "passive"))
      (node (ref "MODE") (pin "2") (pinfunction "2_2") (pintype "passive"))
      (node (ref "R17") (pin "2") (pinfunction "2_2") (pintype "passive"))
      (node (ref "STM32F405RGT6") (pin "9") (pinfunction "PC1_9") (pintype "bidirectional"))
    )
    (net (code "65") (name "PUSH_IN_3") (class "Default")
      (node (ref "STM32F405RGT6") (pin "11") (pinfunction "PC3/SPI2_MOSI_11") (pintype "bidirectional"))
    )
    (net (code "66") (name "RESET") (class "Default")
      (node (ref "C13") (pin "2") (pinfunction "2_2") (pintype "passive"))
      (node (ref "RESET") (pin "1") (pinfunction "1_1") (pintype "passive"))
      (node (ref "RESET") (pin "2") (pinfunction "2_2") (pintype "passive"))
      (node (ref "STM32F405RGT6") (pin "7") (pinfunction "NRST_7") (pintype "bidirectional"))
    )
    (net (code "67") (name "SCK") (class "Default")
      (node (ref "ICM20689") (pin "23") (pinfunction "SCL/SCLK_23") (pintype "input"))
      (node (ref "STM32F405RGT6") (pin "51") (pinfunction "PC10_51") (pintype "bidirectional"))
    )
    (net (code "68") (name "SENSOR_FL") (class "Default")
      (node (ref "J1") (pin "4") (pinfunction "4_4") (pintype "passive"))
      (node (ref "STM32F405RGT6") (pin "16") (pinfunction "PA2/USART2_TX_16") (pintype "bidirectional"))
    )
    (net (code "69") (name "SENSOR_FR") (class "Default")
      (node (ref "J1") (pin "6") (pinfunction "6_6") (pintype "passive"))
      (node (ref "STM32F405RGT6") (pin "14") (pinfunction "PA0/WKUP_14") (pintype "bidirectional"))
    )
    (net (code "70") (name "SENSOR_L") (class "Default")
      (node (ref "J1") (pin "3") (pinfunction "3_3") (pintype "passive"))
      (node (ref "STM32F405RGT6") (pin "17") (pinfunction "PA3/USART2_RX_17") (pintype "bidirectional"))
    )
    (net (code "71") (name "SENSOR_R") (class "Default")
      (node (ref "J1") (pin "5") (pinfunction "5_5") (pintype "passive"))
      (node (ref "STM32F405RGT6") (pin "15") (pinfunction "PA1/USART2_RTS_15") (pintype "bidirectional"))
    )
    (net (code "72") (name "SW-POWER") (class "Default")
      (node (ref "POWER") (pin "2") (pinfunction "2_2") (pintype "passive"))
      (node (ref "STM32F405RGT6") (pin "10") (pinfunction "PC2/SPI2_MISO_10") (pintype "bidirectional"))
    )
    (net (code "73") (name "SWCL") (class "Default")
      (node (ref "JP1") (pin "3") (pinfunction "3_3") (pintype "passive"))
      (node (ref "STM32F405RGT6") (pin "49") (pinfunction "PA14/JTCK-SWCLK_49") (pintype "bidirectional"))
    )
    (net (code "74") (name "SWDIO") (class "Default")
      (node (ref "JP1") (pin "5") (pinfunction "5_5") (pintype "passive"))
      (node (ref "STM32F405RGT6") (pin "46") (pinfunction "PA13/JMS-SWDIO_46") (pintype "bidirectional"))
    )
    (net (code "75") (name "VOL_CHECK") (class "Default")
      (node (ref "R22") (pin "1") (pinfunction "1_1") (pintype "passive"))
      (node (ref "R23") (pin "2") (pinfunction "2_2") (pintype "passive"))
      (node (ref "STM32F405RGT6") (pin "8") (pinfunction "PC0_8") (pintype "bidirectional"))
    )
    (net (code "76") (name "unconnected-(ICM20689-INT-Pad12)") (class "Default")
      (node (ref "ICM20689") (pin "12") (pinfunction "INT_12") (pintype "output"))
    )
    (net (code "77") (name "unconnected-(STM32F405RGT6-PA4{slash}USART2_CK-Pad20)") (class "Default")
      (node (ref "STM32F405RGT6") (pin "20") (pinfunction "PA4/USART2_CK_20") (pintype "bidirectional"))
    )
    (net (code "78") (name "unconnected-(STM32F405RGT6-PA7{slash}SPI1_MOSI-Pad23)") (class "Default")
      (node (ref "STM32F405RGT6") (pin "23") (pinfunction "PA7/SPI1_MOSI_23") (pintype "bidirectional"))
    )
    (net (code "79") (name "unconnected-(STM32F405RGT6-PA8-Pad41)") (class "Default")
      (node (ref "STM32F405RGT6") (pin "41") (pinfunction "PA8_41") (pintype "bidirectional"))
    )
    (net (code "80") (name "unconnected-(STM32F405RGT6-PB3-Pad55)") (class "Default")
      (node (ref "STM32F405RGT6") (pin "55") (pinfunction "PB3_55") (pintype "bidirectional"))
    )
    (net (code "81") (name "unconnected-(STM32F405RGT6-PB8-Pad61)") (class "Default")
      (node (ref "STM32F405RGT6") (pin "61") (pinfunction "PB8_61") (pintype "bidirectional"))
    )
    (net (code "82") (name "unconnected-(STM32F405RGT6-PB9-Pad62)") (class "Default")
      (node (ref "STM32F405RGT6") (pin "62") (pinfunction "PB9_62") (pintype "bidirectional"))
    )
    (net (code "83") (name "unconnected-(STM32F405RGT6-PB14-Pad35)") (class "Default")
      (node (ref "STM32F405RGT6") (pin "35") (pinfunction "PB14_35") (pintype "bidirectional"))
    )
    (net (code "84") (name "unconnected-(STM32F405RGT6-PC8-Pad39)") (class "Default")
      (node (ref "STM32F405RGT6") (pin "39") (pinfunction "PC8_39") (pintype "bidirectional"))
    )
    (net (code "85") (name "unconnected-(STM32F405RGT6-PC9-Pad40)") (class "Default")
      (node (ref "STM32F405RGT6") (pin "40") (pinfunction "PC9_40") (pintype "bidirectional"))
    )
    (net (code "86") (name "unconnected-(STM32F405RGT6-PC13{slash}RTC_OUT-Pad2)") (class "Default")
      (node (ref "STM32F405RGT6") (pin "2") (pinfunction "PC13/RTC_OUT_2") (pintype "bidirectional"))
    )
  )
)
